# auto.net
KiCad netlist of a schematic drawn in EAGLE
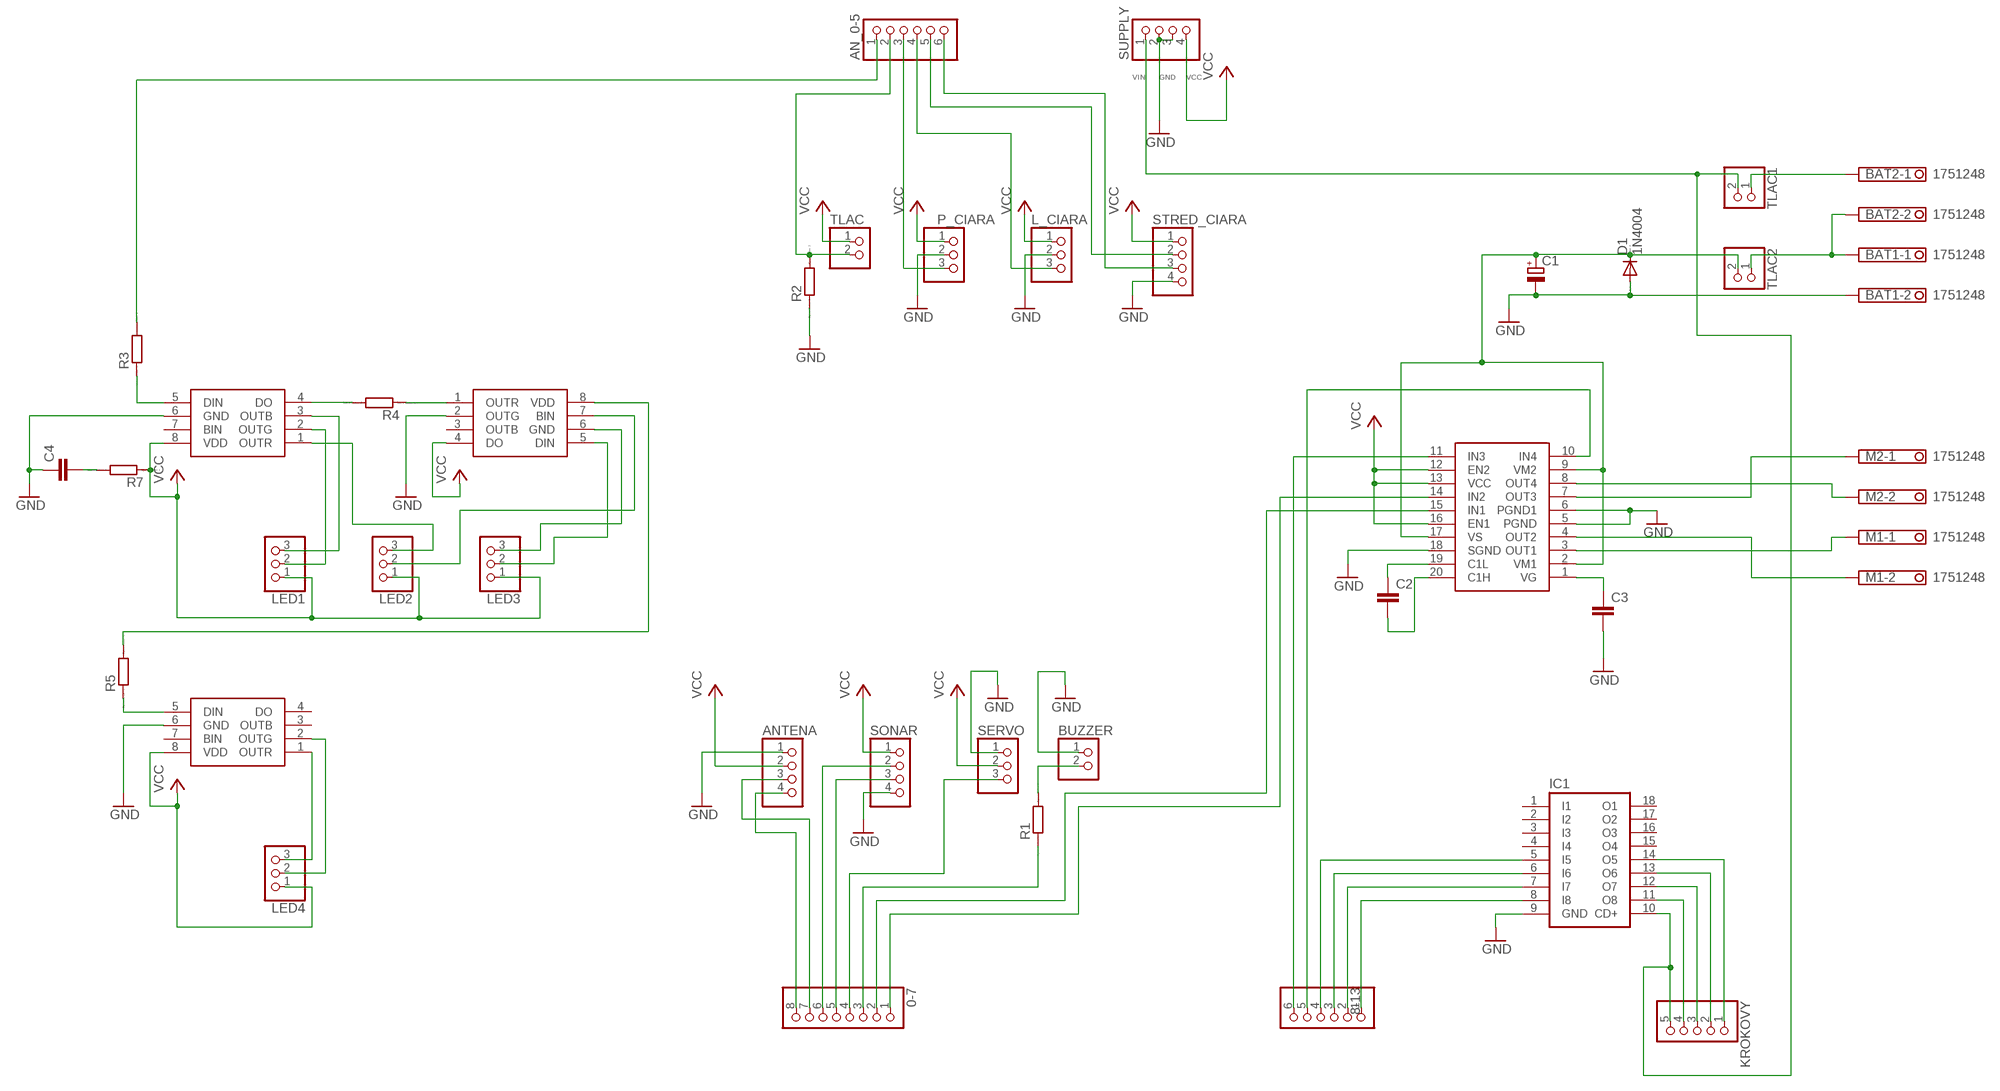
[diagram p0: schematic, sheet 1]

(export (version "E")
  (design (tool "Eeschema 10.0.6"))
  (components
    (comp (ref "0-7")
      (value "PINHD-1X8")
      (footprint "eagle-import:1X08")
      (libsource (lib "eagle-import") (part "PINHD-1X8"))
    )
    (comp (ref "8-13")
      (value "PINHD-1X6")
      (footprint "eagle-import:1X06")
      (libsource (lib "eagle-import") (part "PINHD-1X6"))
    )
    (comp (ref "ANTENA")
      (value "PINHD-1X4")
      (footprint "eagle-import:1X04")
      (libsource (lib "eagle-import") (part "PINHD-1X4"))
    )
    (comp (ref "AN_0-5")
      (value "PINHD-1X6")
      (footprint "eagle-import:1X06")
      (libsource (lib "eagle-import") (part "PINHD-1X6"))
    )
    (comp (ref "BAT1")
      (value "1751248")
      (footprint "eagle-import:1751248")
      (libsource (lib "eagle-import") (part "1751248"))
    )
    (comp (ref "BAT2")
      (value "1751248")
      (footprint "eagle-import:1751248")
      (libsource (lib "eagle-import") (part "1751248"))
    )
    (comp (ref "BUZZER")
      (value "PINHD-1X2")
      (footprint "eagle-import:1X02")
      (libsource (lib "eagle-import") (part "PINHD-1X2"))
    )
    (comp (ref "C1")
      (value "CPOL-EUE3.5-8")
      (footprint "eagle-import:E3,5-8")
      (libsource (lib "eagle-import") (part "CPOL-EUE3.5-8"))
    )
    (comp (ref "C2")
      (value "C-EU050-024X044")
      (footprint "eagle-import:C050-024X044")
      (libsource (lib "eagle-import") (part "C-EU050-024X044"))
    )
    (comp (ref "C3")
      (value "C-EU050-024X044")
      (footprint "eagle-import:C050-024X044")
      (libsource (lib "eagle-import") (part "C-EU050-024X044"))
    )
    (comp (ref "C4")
      (value "C-EU050-024X044")
      (footprint "eagle-import:C050-024X044")
      (libsource (lib "eagle-import") (part "C-EU050-024X044"))
    )
    (comp (ref "D1")
      (value "1N4004")
      (footprint "eagle-import:DO41-10")
      (libsource (lib "eagle-import") (part "1N4004"))
    )
    (comp (ref "IC1")
      (value "ULN2804A")
      (footprint "eagle-import:DIL18")
      (libsource (lib "eagle-import") (part "ULN2804A"))
    )
    (comp (ref "KROKOVY")
      (value "PINHD-1X5")
      (footprint "eagle-import:1X05")
      (libsource (lib "eagle-import") (part "PINHD-1X5"))
    )
    (comp (ref "LED1")
      (value "PINHD-1X3")
      (footprint "eagle-import:1X03")
      (libsource (lib "eagle-import") (part "PINHD-1X3"))
    )
    (comp (ref "LED2")
      (value "PINHD-1X3")
      (footprint "eagle-import:1X03")
      (libsource (lib "eagle-import") (part "PINHD-1X3"))
    )
    (comp (ref "LED3")
      (value "PINHD-1X3")
      (footprint "eagle-import:1X03")
      (libsource (lib "eagle-import") (part "PINHD-1X3"))
    )
    (comp (ref "LED4")
      (value "PINHD-1X3")
      (footprint "eagle-import:1X03")
      (libsource (lib "eagle-import") (part "PINHD-1X3"))
    )
    (comp (ref "L_CIARA")
      (value "PINHD-1X3")
      (footprint "eagle-import:1X03")
      (libsource (lib "eagle-import") (part "PINHD-1X3"))
    )
    (comp (ref "M1")
      (value "1751248")
      (footprint "eagle-import:1751248")
      (libsource (lib "eagle-import") (part "1751248"))
    )
    (comp (ref "M2")
      (value "1751248")
      (footprint "eagle-import:1751248")
      (libsource (lib "eagle-import") (part "1751248"))
    )
    (comp (ref "P_CIARA")
      (value "PINHD-1X3")
      (footprint "eagle-import:1X03")
      (libsource (lib "eagle-import") (part "PINHD-1X3"))
    )
    (comp (ref "R1")
      (value "R0207/10")
      (footprint "eagle-import:0207_10")
      (libsource (lib "eagle-import") (part "R0207/10"))
    )
    (comp (ref "R2")
      (value "R0207/10")
      (footprint "eagle-import:0207_10")
      (libsource (lib "eagle-import") (part "R0207/10"))
    )
    (comp (ref "R3")
      (value "R0207/10")
      (footprint "eagle-import:0207_10")
      (libsource (lib "eagle-import") (part "R0207/10"))
    )
    (comp (ref "R4")
      (value "R0207/10")
      (footprint "eagle-import:0207_10")
      (libsource (lib "eagle-import") (part "R0207/10"))
    )
    (comp (ref "R5")
      (value "R0207/10")
      (footprint "eagle-import:0207_10")
      (libsource (lib "eagle-import") (part "R0207/10"))
    )
    (comp (ref "R7")
      (value "R0207/10")
      (footprint "eagle-import:0207_10")
      (libsource (lib "eagle-import") (part "R0207/10"))
    )
    (comp (ref "SERVO")
      (value "PINHD-1X3")
      (footprint "eagle-import:1X03")
      (libsource (lib "eagle-import") (part "PINHD-1X3"))
    )
    (comp (ref "SONAR")
      (value "PINHD-1X4")
      (footprint "eagle-import:1X04")
      (libsource (lib "eagle-import") (part "PINHD-1X4"))
    )
    (comp (ref "STRED_CIARA")
      (value "PINHD-1X4")
      (footprint "eagle-import:1X04")
      (libsource (lib "eagle-import") (part "PINHD-1X4"))
    )
    (comp (ref "SUPPLY")
      (value "PINHD-1X4")
      (footprint "eagle-import:1X04")
      (libsource (lib "eagle-import") (part "PINHD-1X4"))
    )
    (comp (ref "TLAC")
      (value "PINHD-1X2")
      (footprint "eagle-import:1X02")
      (libsource (lib "eagle-import") (part "PINHD-1X2"))
    )
    (comp (ref "TLAC1")
      (value "PINHD-1X2")
      (footprint "eagle-import:1X02")
      (libsource (lib "eagle-import") (part "PINHD-1X2"))
    )
    (comp (ref "TLAC2")
      (value "PINHD-1X2")
      (footprint "eagle-import:1X02")
      (libsource (lib "eagle-import") (part "PINHD-1X2"))
    )
    (comp (ref "U$1")
      (value "LV8406")
      (footprint "eagle-import:TSSOP20")
      (libsource (lib "eagle-import") (part "LV8406"))
    )
    (comp (ref "U$2")
      (value "WS2518B")
      (footprint "eagle-import:SOP08")
      (libsource (lib "eagle-import") (part "WS2518B"))
    )
    (comp (ref "U$3")
      (value "WS2518B")
      (footprint "eagle-import:SOP08")
      (libsource (lib "eagle-import") (part "WS2518B"))
    )
    (comp (ref "U$4")
      (value "WS2518B")
      (footprint "eagle-import:SOP08")
      (libsource (lib "eagle-import") (part "WS2518B"))
    )
  )
  (nets
    (net (code "1") (name "/VIN") (class "Default")
      (node (ref "IC1") (pin "10") (pinfunction "CD+_10") (pintype "passive"))
      (node (ref "KROKOVY") (pin "5") (pinfunction "5_5") (pintype "passive"))
      (node (ref "SUPPLY") (pin "1") (pinfunction "1_1") (pintype "passive"))
      (node (ref "TLAC1") (pin "2") (pinfunction "2_2") (pintype "passive"))
    )
    (net (code "2") (name "GND") (class "Default")
      (node (ref "ANTENA") (pin "1") (pinfunction "1_1") (pintype "passive"))
      (node (ref "BAT1") (pin "2") (pinfunction "K_2") (pintype "passive"))
      (node (ref "BUZZER") (pin "1") (pinfunction "1_1") (pintype "passive"))
      (node (ref "C1") (pin "-") (pinfunction "-_-") (pintype "passive"))
      (node (ref "C3") (pin "2") (pinfunction "2_2") (pintype "passive"))
      (node (ref "C4") (pin "1") (pinfunction "1_1") (pintype "passive"))
      (node (ref "D1") (pin "A") (pinfunction "A_A") (pintype "passive"))
      (node (ref "IC1") (pin "9") (pinfunction "GND_9") (pintype "power_in"))
      (node (ref "L_CIARA") (pin "2") (pinfunction "2_2") (pintype "passive"))
      (node (ref "P_CIARA") (pin "2") (pinfunction "2_2") (pintype "passive"))
      (node (ref "R2") (pin "1") (pinfunction "1_1") (pintype "passive"))
      (node (ref "SERVO") (pin "1") (pinfunction "1_1") (pintype "passive"))
      (node (ref "SONAR") (pin "4") (pinfunction "4_4") (pintype "passive"))
      (node (ref "STRED_CIARA") (pin "4") (pinfunction "4_4") (pintype "passive"))
      (node (ref "SUPPLY") (pin "2") (pinfunction "2_2") (pintype "passive"))
      (node (ref "SUPPLY") (pin "3") (pinfunction "3_3") (pintype "passive"))
      (node (ref "U$1") (pin "18") (pinfunction "SGND_18") (pintype "bidirectional"))
      (node (ref "U$1") (pin "5") (pinfunction "PGND_5") (pintype "bidirectional"))
      (node (ref "U$1") (pin "6") (pinfunction "PGND1_6") (pintype "bidirectional"))
      (node (ref "U$2") (pin "6") (pinfunction "GND_6") (pintype "bidirectional"))
      (node (ref "U$3") (pin "2") (pinfunction "OUTG_2") (pintype "bidirectional"))
      (node (ref "U$4") (pin "6") (pinfunction "GND_6") (pintype "bidirectional"))
    )
    (net (code "3") (name "Net-(0-7-Pad3)") (class "Default")
      (node (ref "0-7") (pin "3") (pinfunction "3_3") (pintype "passive"))
      (node (ref "R1") (pin "1") (pinfunction "1_1") (pintype "passive"))
    )
    (net (code "4") (name "Net-(0-7-Pad4)") (class "Default")
      (node (ref "0-7") (pin "4") (pinfunction "4_4") (pintype "passive"))
      (node (ref "SERVO") (pin "3") (pinfunction "3_3") (pintype "passive"))
    )
    (net (code "5") (name "Net-(0-7-Pad5)") (class "Default")
      (node (ref "0-7") (pin "5") (pinfunction "5_5") (pintype "passive"))
      (node (ref "SONAR") (pin "3") (pinfunction "3_3") (pintype "passive"))
    )
    (net (code "6") (name "Net-(0-7-Pad6)") (class "Default")
      (node (ref "0-7") (pin "6") (pinfunction "6_6") (pintype "passive"))
      (node (ref "SONAR") (pin "2") (pinfunction "2_2") (pintype "passive"))
    )
    (net (code "7") (name "Net-(0-7-Pad7)") (class "Default")
      (node (ref "0-7") (pin "7") (pinfunction "7_7") (pintype "passive"))
      (node (ref "ANTENA") (pin "3") (pinfunction "3_3") (pintype "passive"))
    )
    (net (code "8") (name "Net-(0-7-Pad8)") (class "Default")
      (node (ref "0-7") (pin "8") (pinfunction "8_8") (pintype "passive"))
      (node (ref "ANTENA") (pin "4") (pinfunction "4_4") (pintype "passive"))
    )
    (net (code "9") (name "Net-(AN_0-5-Pad1)") (class "Default")
      (node (ref "AN_0-5") (pin "1") (pinfunction "1_1") (pintype "passive"))
      (node (ref "R3") (pin "2") (pinfunction "2_2") (pintype "passive"))
    )
    (net (code "10") (name "Net-(AN_0-5-Pad2)") (class "Default")
      (node (ref "AN_0-5") (pin "2") (pinfunction "2_2") (pintype "passive"))
      (node (ref "R2") (pin "2") (pinfunction "2_2") (pintype "passive"))
      (node (ref "TLAC") (pin "2") (pinfunction "2_2") (pintype "passive"))
    )
    (net (code "11") (name "Net-(AN_0-5-Pad3)") (class "Default")
      (node (ref "AN_0-5") (pin "3") (pinfunction "3_3") (pintype "passive"))
      (node (ref "P_CIARA") (pin "3") (pinfunction "3_3") (pintype "passive"))
    )
    (net (code "12") (name "Net-(AN_0-5-Pad4)") (class "Default")
      (node (ref "AN_0-5") (pin "4") (pinfunction "4_4") (pintype "passive"))
      (node (ref "L_CIARA") (pin "3") (pinfunction "3_3") (pintype "passive"))
    )
    (net (code "13") (name "Net-(AN_0-5-Pad5)") (class "Default")
      (node (ref "AN_0-5") (pin "5") (pinfunction "5_5") (pintype "passive"))
      (node (ref "STRED_CIARA") (pin "2") (pinfunction "2_2") (pintype "passive"))
    )
    (net (code "14") (name "Net-(AN_0-5-Pad6)") (class "Default")
      (node (ref "AN_0-5") (pin "6") (pinfunction "6_6") (pintype "passive"))
      (node (ref "STRED_CIARA") (pin "3") (pinfunction "3_3") (pintype "passive"))
    )
    (net (code "15") (name "Net-(BAT1A-K)") (class "Default")
      (node (ref "BAT1") (pin "1") (pinfunction "K_1") (pintype "passive"))
      (node (ref "BAT2") (pin "2") (pinfunction "K_2") (pintype "passive"))
      (node (ref "TLAC2") (pin "1") (pinfunction "1_1") (pintype "passive"))
    )
    (net (code "16") (name "Net-(BAT2A-K)") (class "Default")
      (node (ref "BAT2") (pin "1") (pinfunction "K_1") (pintype "passive"))
      (node (ref "TLAC1") (pin "1") (pinfunction "1_1") (pintype "passive"))
    )
    (net (code "17") (name "Net-(BUZZER-Pad2)") (class "Default")
      (node (ref "BUZZER") (pin "2") (pinfunction "2_2") (pintype "passive"))
      (node (ref "R1") (pin "2") (pinfunction "2_2") (pintype "passive"))
    )
    (net (code "18") (name "Net-(C4-Pad2)") (class "Default")
      (node (ref "C4") (pin "2") (pinfunction "2_2") (pintype "passive"))
      (node (ref "R7") (pin "2") (pinfunction "2_2") (pintype "passive"))
    )
    (net (code "19") (name "Net-(IC1-I5)") (class "Default")
      (node (ref "8-13") (pin "4") (pinfunction "4_4") (pintype "passive"))
      (node (ref "IC1") (pin "5") (pinfunction "I5_5") (pintype "input"))
    )
    (net (code "20") (name "Net-(IC1-I6)") (class "Default")
      (node (ref "8-13") (pin "3") (pinfunction "3_3") (pintype "passive"))
      (node (ref "IC1") (pin "6") (pinfunction "I6_6") (pintype "input"))
    )
    (net (code "21") (name "Net-(IC1-I7)") (class "Default")
      (node (ref "8-13") (pin "2") (pinfunction "2_2") (pintype "passive"))
      (node (ref "IC1") (pin "7") (pinfunction "I7_7") (pintype "input"))
    )
    (net (code "22") (name "Net-(IC1-I8)") (class "Default")
      (node (ref "8-13") (pin "1") (pinfunction "1_1") (pintype "passive"))
      (node (ref "IC1") (pin "8") (pinfunction "I8_8") (pintype "input"))
    )
    (net (code "23") (name "Net-(IC1-O5)") (class "Default")
      (node (ref "IC1") (pin "14") (pinfunction "O5_14") (pintype "open_collector"))
      (node (ref "KROKOVY") (pin "1") (pinfunction "1_1") (pintype "passive"))
    )
    (net (code "24") (name "Net-(IC1-O6)") (class "Default")
      (node (ref "IC1") (pin "13") (pinfunction "O6_13") (pintype "open_collector"))
      (node (ref "KROKOVY") (pin "2") (pinfunction "2_2") (pintype "passive"))
    )
    (net (code "25") (name "Net-(IC1-O7)") (class "Default")
      (node (ref "IC1") (pin "12") (pinfunction "O7_12") (pintype "open_collector"))
      (node (ref "KROKOVY") (pin "3") (pinfunction "3_3") (pintype "passive"))
    )
    (net (code "26") (name "Net-(IC1-O8)") (class "Default")
      (node (ref "IC1") (pin "11") (pinfunction "O8_11") (pintype "open_collector"))
      (node (ref "KROKOVY") (pin "4") (pinfunction "4_4") (pintype "passive"))
    )
    (net (code "27") (name "Net-(M1A-K)") (class "Default")
      (node (ref "M1") (pin "1") (pinfunction "K_1") (pintype "passive"))
      (node (ref "U$1") (pin "3") (pinfunction "OUT1_3") (pintype "bidirectional"))
    )
    (net (code "28") (name "Net-(M1B-K)") (class "Default")
      (node (ref "M1") (pin "2") (pinfunction "K_2") (pintype "passive"))
      (node (ref "U$1") (pin "4") (pinfunction "OUT2_4") (pintype "bidirectional"))
    )
    (net (code "29") (name "Net-(M2A-K)") (class "Default")
      (node (ref "M2") (pin "1") (pinfunction "K_1") (pintype "passive"))
      (node (ref "U$1") (pin "7") (pinfunction "OUT3_7") (pintype "bidirectional"))
    )
    (net (code "30") (name "Net-(M2B-K)") (class "Default")
      (node (ref "M2") (pin "2") (pinfunction "K_2") (pintype "passive"))
      (node (ref "U$1") (pin "8") (pinfunction "OUT4_8") (pintype "bidirectional"))
    )
    (net (code "31") (name "Net-(U$1-C1H)") (class "Default")
      (node (ref "C2") (pin "2") (pinfunction "2_2") (pintype "passive"))
      (node (ref "U$1") (pin "20") (pinfunction "C1H_20") (pintype "bidirectional"))
    )
    (net (code "32") (name "Net-(U$1-C1L)") (class "Default")
      (node (ref "C2") (pin "1") (pinfunction "1_1") (pintype "passive"))
      (node (ref "U$1") (pin "19") (pinfunction "C1L_19") (pintype "bidirectional"))
    )
    (net (code "33") (name "Net-(U$1-IN1)") (class "Default")
      (node (ref "0-7") (pin "2") (pinfunction "2_2") (pintype "passive"))
      (node (ref "U$1") (pin "15") (pinfunction "IN1_15") (pintype "bidirectional"))
    )
    (net (code "34") (name "Net-(U$1-IN2)") (class "Default")
      (node (ref "0-7") (pin "1") (pinfunction "1_1") (pintype "passive"))
      (node (ref "U$1") (pin "14") (pinfunction "IN2_14") (pintype "bidirectional"))
    )
    (net (code "35") (name "Net-(U$1-IN3)") (class "Default")
      (node (ref "8-13") (pin "6") (pinfunction "6_6") (pintype "passive"))
      (node (ref "U$1") (pin "11") (pinfunction "IN3_11") (pintype "bidirectional"))
    )
    (net (code "36") (name "Net-(U$1-IN4)") (class "Default")
      (node (ref "8-13") (pin "5") (pinfunction "5_5") (pintype "passive"))
      (node (ref "U$1") (pin "10") (pinfunction "IN4_10") (pintype "bidirectional"))
    )
    (net (code "37") (name "Net-(U$1-VG)") (class "Default")
      (node (ref "C3") (pin "1") (pinfunction "1_1") (pintype "passive"))
      (node (ref "U$1") (pin "1") (pinfunction "VG_1") (pintype "bidirectional"))
    )
    (net (code "38") (name "Net-(U$1-VM1)") (class "Default")
      (node (ref "C1") (pin "+") (pinfunction "+_+") (pintype "passive"))
      (node (ref "D1") (pin "C") (pinfunction "C_C") (pintype "passive"))
      (node (ref "TLAC2") (pin "2") (pinfunction "2_2") (pintype "passive"))
      (node (ref "U$1") (pin "17") (pinfunction "VS_17") (pintype "bidirectional"))
      (node (ref "U$1") (pin "2") (pinfunction "VM1_2") (pintype "bidirectional"))
      (node (ref "U$1") (pin "9") (pinfunction "VM2_9") (pintype "bidirectional"))
    )
    (net (code "39") (name "Net-(U$2-DIN)") (class "Default")
      (node (ref "R3") (pin "1") (pinfunction "1_1") (pintype "passive"))
      (node (ref "U$2") (pin "5") (pinfunction "DIN_5") (pintype "bidirectional"))
    )
    (net (code "40") (name "Net-(U$2-DO)") (class "Default")
      (node (ref "R4") (pin "2") (pinfunction "2_2") (pintype "passive"))
      (node (ref "U$2") (pin "4") (pinfunction "DO_4") (pintype "bidirectional"))
    )
    (net (code "41") (name "Net-(U$2-OUTB)") (class "Default")
      (node (ref "LED1") (pin "3") (pinfunction "3_3") (pintype "passive"))
      (node (ref "U$2") (pin "3") (pinfunction "OUTB_3") (pintype "bidirectional"))
    )
    (net (code "42") (name "Net-(U$2-OUTG)") (class "Default")
      (node (ref "LED1") (pin "2") (pinfunction "2_2") (pintype "passive"))
      (node (ref "U$2") (pin "2") (pinfunction "OUTG_2") (pintype "bidirectional"))
    )
    (net (code "43") (name "Net-(U$2-OUTR)") (class "Default")
      (node (ref "LED2") (pin "3") (pinfunction "3_3") (pintype "passive"))
      (node (ref "U$2") (pin "1") (pinfunction "OUTR_1") (pintype "bidirectional"))
    )
    (net (code "44") (name "Net-(U$3-BIN)") (class "Default")
      (node (ref "LED2") (pin "2") (pinfunction "2_2") (pintype "passive"))
      (node (ref "U$3") (pin "7") (pinfunction "BIN_7") (pintype "bidirectional"))
    )
    (net (code "45") (name "Net-(U$3-DIN)") (class "Default")
      (node (ref "LED3") (pin "2") (pinfunction "2_2") (pintype "passive"))
      (node (ref "U$3") (pin "5") (pinfunction "DIN_5") (pintype "bidirectional"))
    )
    (net (code "46") (name "Net-(U$3-GND)") (class "Default")
      (node (ref "LED3") (pin "3") (pinfunction "3_3") (pintype "passive"))
      (node (ref "U$3") (pin "6") (pinfunction "GND_6") (pintype "bidirectional"))
    )
    (net (code "47") (name "Net-(U$3-OUTR)") (class "Default")
      (node (ref "R4") (pin "1") (pinfunction "1_1") (pintype "passive"))
      (node (ref "U$3") (pin "1") (pinfunction "OUTR_1") (pintype "bidirectional"))
    )
    (net (code "48") (name "Net-(U$3-VDD)") (class "Default")
      (node (ref "R5") (pin "2") (pinfunction "2_2") (pintype "passive"))
      (node (ref "U$3") (pin "8") (pinfunction "VDD_8") (pintype "bidirectional"))
    )
    (net (code "49") (name "Net-(U$4-DIN)") (class "Default")
      (node (ref "R5") (pin "1") (pinfunction "1_1") (pintype "passive"))
      (node (ref "U$4") (pin "5") (pinfunction "DIN_5") (pintype "bidirectional"))
    )
    (net (code "50") (name "Net-(U$4-OUTG)") (class "Default")
      (node (ref "LED4") (pin "2") (pinfunction "2_2") (pintype "passive"))
      (node (ref "U$4") (pin "2") (pinfunction "OUTG_2") (pintype "bidirectional"))
    )
    (net (code "51") (name "Net-(U$4-OUTR)") (class "Default")
      (node (ref "LED4") (pin "3") (pinfunction "3_3") (pintype "passive"))
      (node (ref "U$4") (pin "1") (pinfunction "OUTR_1") (pintype "bidirectional"))
    )
    (net (code "52") (name "VCC") (class "Default")
      (node (ref "ANTENA") (pin "2") (pinfunction "2_2") (pintype "passive"))
      (node (ref "LED1") (pin "1") (pinfunction "1_1") (pintype "passive"))
      (node (ref "LED2") (pin "1") (pinfunction "1_1") (pintype "passive"))
      (node (ref "LED3") (pin "1") (pinfunction "1_1") (pintype "passive"))
      (node (ref "LED4") (pin "1") (pinfunction "1_1") (pintype "passive"))
      (node (ref "L_CIARA") (pin "1") (pinfunction "1_1") (pintype "passive"))
      (node (ref "P_CIARA") (pin "1") (pinfunction "1_1") (pintype "passive"))
      (node (ref "R7") (pin "1") (pinfunction "1_1") (pintype "passive"))
      (node (ref "SERVO") (pin "2") (pinfunction "2_2") (pintype "passive"))
      (node (ref "SONAR") (pin "1") (pinfunction "1_1") (pintype "passive"))
      (node (ref "STRED_CIARA") (pin "1") (pinfunction "1_1") (pintype "passive"))
      (node (ref "SUPPLY") (pin "4") (pinfunction "4_4") (pintype "passive"))
      (node (ref "TLAC") (pin "1") (pinfunction "1_1") (pintype "passive"))
      (node (ref "U$1") (pin "12") (pinfunction "EN2_12") (pintype "bidirectional"))
      (node (ref "U$1") (pin "13") (pinfunction "VCC_13") (pintype "bidirectional"))
      (node (ref "U$1") (pin "16") (pinfunction "EN1_16") (pintype "bidirectional"))
      (node (ref "U$2") (pin "8") (pinfunction "VDD_8") (pintype "bidirectional"))
      (node (ref "U$3") (pin "4") (pinfunction "DO_4") (pintype "bidirectional"))
      (node (ref "U$4") (pin "8") (pinfunction "VDD_8") (pintype "bidirectional"))
    )
    (net (code "53") (name "unconnected-(IC1-I1-Pad1)") (class "Default")
      (node (ref "IC1") (pin "1") (pinfunction "I1_1") (pintype "input"))
    )
    (net (code "54") (name "unconnected-(IC1-I2-Pad2)") (class "Default")
      (node (ref "IC1") (pin "2") (pinfunction "I2_2") (pintype "input"))
    )
    (net (code "55") (name "unconnected-(IC1-I3-Pad3)") (class "Default")
      (node (ref "IC1") (pin "3") (pinfunction "I3_3") (pintype "input"))
    )
    (net (code "56") (name "unconnected-(IC1-I4-Pad4)") (class "Default")
      (node (ref "IC1") (pin "4") (pinfunction "I4_4") (pintype "input"))
    )
    (net (code "57") (name "unconnected-(IC1-O1-Pad18)") (class "Default")
      (node (ref "IC1") (pin "18") (pinfunction "O1_18") (pintype "open_collector"))
    )
    (net (code "58") (name "unconnected-(IC1-O2-Pad17)") (class "Default")
      (node (ref "IC1") (pin "17") (pinfunction "O2_17") (pintype "open_collector"))
    )
    (net (code "59") (name "unconnected-(IC1-O3-Pad16)") (class "Default")
      (node (ref "IC1") (pin "16") (pinfunction "O3_16") (pintype "open_collector"))
    )
    (net (code "60") (name "unconnected-(IC1-O4-Pad15)") (class "Default")
      (node (ref "IC1") (pin "15") (pinfunction "O4_15") (pintype "open_collector"))
    )
    (net (code "61") (name "unconnected-(U$2-BIN-Pad7)") (class "Default")
      (node (ref "U$2") (pin "7") (pinfunction "BIN_7") (pintype "bidirectional"))
    )
    (net (code "62") (name "unconnected-(U$3-OUTB-Pad3)") (class "Default")
      (node (ref "U$3") (pin "3") (pinfunction "OUTB_3") (pintype "bidirectional"))
    )
    (net (code "63") (name "unconnected-(U$4-BIN-Pad7)") (class "Default")
      (node (ref "U$4") (pin "7") (pinfunction "BIN_7") (pintype "bidirectional"))
    )
    (net (code "64") (name "unconnected-(U$4-DO-Pad4)") (class "Default")
      (node (ref "U$4") (pin "4") (pinfunction "DO_4") (pintype "bidirectional"))
    )
    (net (code "65") (name "unconnected-(U$4-OUTB-Pad3)") (class "Default")
      (node (ref "U$4") (pin "3") (pinfunction "OUTB_3") (pintype "bidirectional"))
    )
  )
)
